# tssop20.net
KiCad netlist of a schematic drawn in EAGLE
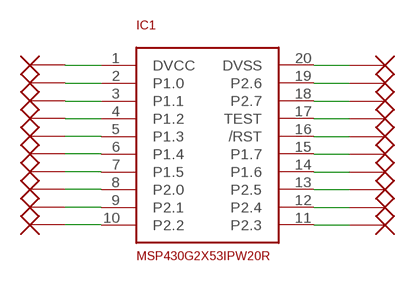
[diagram p0: schematic, sheet 1]

(export (version "E")
  (design (tool "Eeschema 10.0.6"))
  (components
    (comp (ref "IC1")
      (value "MSP430G2X53IPW20R")
      (footprint "eagle-import:TSSOP20")
      (libsource (lib "eagle-import") (part "MSP430G2X53IPW20R"))
    )
    (comp (ref "P1")
      (value "PIN")
      (footprint "eagle-import:PIN")
      (libsource (lib "eagle-import") (part "PIN"))
    )
    (comp (ref "P2")
      (value "PIN")
      (footprint "eagle-import:PIN")
      (libsource (lib "eagle-import") (part "PIN"))
    )
    (comp (ref "P3")
      (value "PIN")
      (footprint "eagle-import:PIN")
      (libsource (lib "eagle-import") (part "PIN"))
    )
    (comp (ref "P4")
      (value "PIN")
      (footprint "eagle-import:PIN")
      (libsource (lib "eagle-import") (part "PIN"))
    )
    (comp (ref "P5")
      (value "PIN")
      (footprint "eagle-import:PIN")
      (libsource (lib "eagle-import") (part "PIN"))
    )
    (comp (ref "P6")
      (value "PIN")
      (footprint "eagle-import:PIN")
      (libsource (lib "eagle-import") (part "PIN"))
    )
    (comp (ref "P7")
      (value "PIN")
      (footprint "eagle-import:PIN")
      (libsource (lib "eagle-import") (part "PIN"))
    )
    (comp (ref "P8")
      (value "PIN")
      (footprint "eagle-import:PIN")
      (libsource (lib "eagle-import") (part "PIN"))
    )
    (comp (ref "P9")
      (value "PIN")
      (footprint "eagle-import:PIN")
      (libsource (lib "eagle-import") (part "PIN"))
    )
    (comp (ref "P10")
      (value "PIN")
      (footprint "eagle-import:PIN")
      (libsource (lib "eagle-import") (part "PIN"))
    )
    (comp (ref "P15")
      (value "PIN")
      (footprint "eagle-import:PIN")
      (libsource (lib "eagle-import") (part "PIN"))
    )
    (comp (ref "P16")
      (value "PIN")
      (footprint "eagle-import:PIN")
      (libsource (lib "eagle-import") (part "PIN"))
    )
    (comp (ref "P17")
      (value "PIN")
      (footprint "eagle-import:PIN")
      (libsource (lib "eagle-import") (part "PIN"))
    )
    (comp (ref "P18")
      (value "PIN")
      (footprint "eagle-import:PIN")
      (libsource (lib "eagle-import") (part "PIN"))
    )
    (comp (ref "P19")
      (value "PIN")
      (footprint "eagle-import:PIN")
      (libsource (lib "eagle-import") (part "PIN"))
    )
    (comp (ref "P20")
      (value "PIN")
      (footprint "eagle-import:PIN")
      (libsource (lib "eagle-import") (part "PIN"))
    )
    (comp (ref "P21")
      (value "PIN")
      (footprint "eagle-import:PIN")
      (libsource (lib "eagle-import") (part "PIN"))
    )
    (comp (ref "P22")
      (value "PIN")
      (footprint "eagle-import:PIN")
      (libsource (lib "eagle-import") (part "PIN"))
    )
    (comp (ref "P23")
      (value "PIN")
      (footprint "eagle-import:PIN")
      (libsource (lib "eagle-import") (part "PIN"))
    )
    (comp (ref "P24")
      (value "PIN")
      (footprint "eagle-import:PIN")
      (libsource (lib "eagle-import") (part "PIN"))
    )
  )
  (nets
    (net (code "1") (name "Net-(IC1-DVCC)") (class "Default")
      (node (ref "IC1") (pin "1") (pinfunction "DVCC_1") (pintype "bidirectional"))
      (node (ref "P1") (pin "P$1") (pinfunction "P$1_P$1") (pintype "bidirectional"))
    )
    (net (code "2") (name "Net-(IC1-DVSS)") (class "Default")
      (node (ref "IC1") (pin "20") (pinfunction "DVSS_20") (pintype "bidirectional"))
      (node (ref "P15") (pin "P$1") (pinfunction "P$1_P$1") (pintype "bidirectional"))
    )
    (net (code "3") (name "Net-(IC1-P1.0)") (class "Default")
      (node (ref "IC1") (pin "2") (pinfunction "P1.0_2") (pintype "bidirectional"))
      (node (ref "P2") (pin "P$1") (pinfunction "P$1_P$1") (pintype "bidirectional"))
    )
    (net (code "4") (name "Net-(IC1-P1.1)") (class "Default")
      (node (ref "IC1") (pin "3") (pinfunction "P1.1_3") (pintype "bidirectional"))
      (node (ref "P3") (pin "P$1") (pinfunction "P$1_P$1") (pintype "bidirectional"))
    )
    (net (code "5") (name "Net-(IC1-P1.2)") (class "Default")
      (node (ref "IC1") (pin "4") (pinfunction "P1.2_4") (pintype "bidirectional"))
      (node (ref "P4") (pin "P$1") (pinfunction "P$1_P$1") (pintype "bidirectional"))
    )
    (net (code "6") (name "Net-(IC1-P1.3)") (class "Default")
      (node (ref "IC1") (pin "5") (pinfunction "P1.3_5") (pintype "bidirectional"))
      (node (ref "P5") (pin "P$1") (pinfunction "P$1_P$1") (pintype "bidirectional"))
    )
    (net (code "7") (name "Net-(IC1-P1.4)") (class "Default")
      (node (ref "IC1") (pin "6") (pinfunction "P1.4_6") (pintype "bidirectional"))
      (node (ref "P6") (pin "P$1") (pinfunction "P$1_P$1") (pintype "bidirectional"))
    )
    (net (code "8") (name "Net-(IC1-P1.5)") (class "Default")
      (node (ref "IC1") (pin "7") (pinfunction "P1.5_7") (pintype "bidirectional"))
      (node (ref "P7") (pin "P$1") (pinfunction "P$1_P$1") (pintype "bidirectional"))
    )
    (net (code "9") (name "Net-(IC1-P1.6)") (class "Default")
      (node (ref "IC1") (pin "14") (pinfunction "P1.6_14") (pintype "bidirectional"))
      (node (ref "P21") (pin "P$1") (pinfunction "P$1_P$1") (pintype "bidirectional"))
    )
    (net (code "10") (name "Net-(IC1-P1.7)") (class "Default")
      (node (ref "IC1") (pin "15") (pinfunction "P1.7_15") (pintype "bidirectional"))
      (node (ref "P20") (pin "P$1") (pinfunction "P$1_P$1") (pintype "bidirectional"))
    )
    (net (code "11") (name "Net-(IC1-P2.0)") (class "Default")
      (node (ref "IC1") (pin "8") (pinfunction "P2.0_8") (pintype "bidirectional"))
      (node (ref "P8") (pin "P$1") (pinfunction "P$1_P$1") (pintype "bidirectional"))
    )
    (net (code "12") (name "Net-(IC1-P2.1)") (class "Default")
      (node (ref "IC1") (pin "9") (pinfunction "P2.1_9") (pintype "bidirectional"))
      (node (ref "P9") (pin "P$1") (pinfunction "P$1_P$1") (pintype "bidirectional"))
    )
    (net (code "13") (name "Net-(IC1-P2.2)") (class "Default")
      (node (ref "IC1") (pin "10") (pinfunction "P2.2_10") (pintype "bidirectional"))
      (node (ref "P10") (pin "P$1") (pinfunction "P$1_P$1") (pintype "bidirectional"))
    )
    (net (code "14") (name "Net-(IC1-P2.3)") (class "Default")
      (node (ref "IC1") (pin "11") (pinfunction "P2.3_11") (pintype "bidirectional"))
      (node (ref "P24") (pin "P$1") (pinfunction "P$1_P$1") (pintype "bidirectional"))
    )
    (net (code "15") (name "Net-(IC1-P2.4)") (class "Default")
      (node (ref "IC1") (pin "12") (pinfunction "P2.4_12") (pintype "bidirectional"))
      (node (ref "P23") (pin "P$1") (pinfunction "P$1_P$1") (pintype "bidirectional"))
    )
    (net (code "16") (name "Net-(IC1-P2.5)") (class "Default")
      (node (ref "IC1") (pin "13") (pinfunction "P2.5_13") (pintype "bidirectional"))
      (node (ref "P22") (pin "P$1") (pinfunction "P$1_P$1") (pintype "bidirectional"))
    )
    (net (code "17") (name "Net-(IC1-P2.6)") (class "Default")
      (node (ref "IC1") (pin "19") (pinfunction "P2.6_19") (pintype "bidirectional"))
      (node (ref "P16") (pin "P$1") (pinfunction "P$1_P$1") (pintype "bidirectional"))
    )
    (net (code "18") (name "Net-(IC1-P2.7)") (class "Default")
      (node (ref "IC1") (pin "18") (pinfunction "P2.7_18") (pintype "bidirectional"))
      (node (ref "P17") (pin "P$1") (pinfunction "P$1_P$1") (pintype "bidirectional"))
    )
    (net (code "19") (name "Net-(IC1-TEST)") (class "Default")
      (node (ref "IC1") (pin "17") (pinfunction "TEST_17") (pintype "bidirectional"))
      (node (ref "P18") (pin "P$1") (pinfunction "P$1_P$1") (pintype "bidirectional"))
    )
    (net (code "20") (name "Net-(IC1-{slash}RST)") (class "Default")
      (node (ref "IC1") (pin "16") (pinfunction "/RST_16") (pintype "bidirectional"))
      (node (ref "P19") (pin "P$1") (pinfunction "P$1_P$1") (pintype "bidirectional"))
    )
  )
)
